# diplom.net
KiCad netlist of a schematic drawn in EAGLE
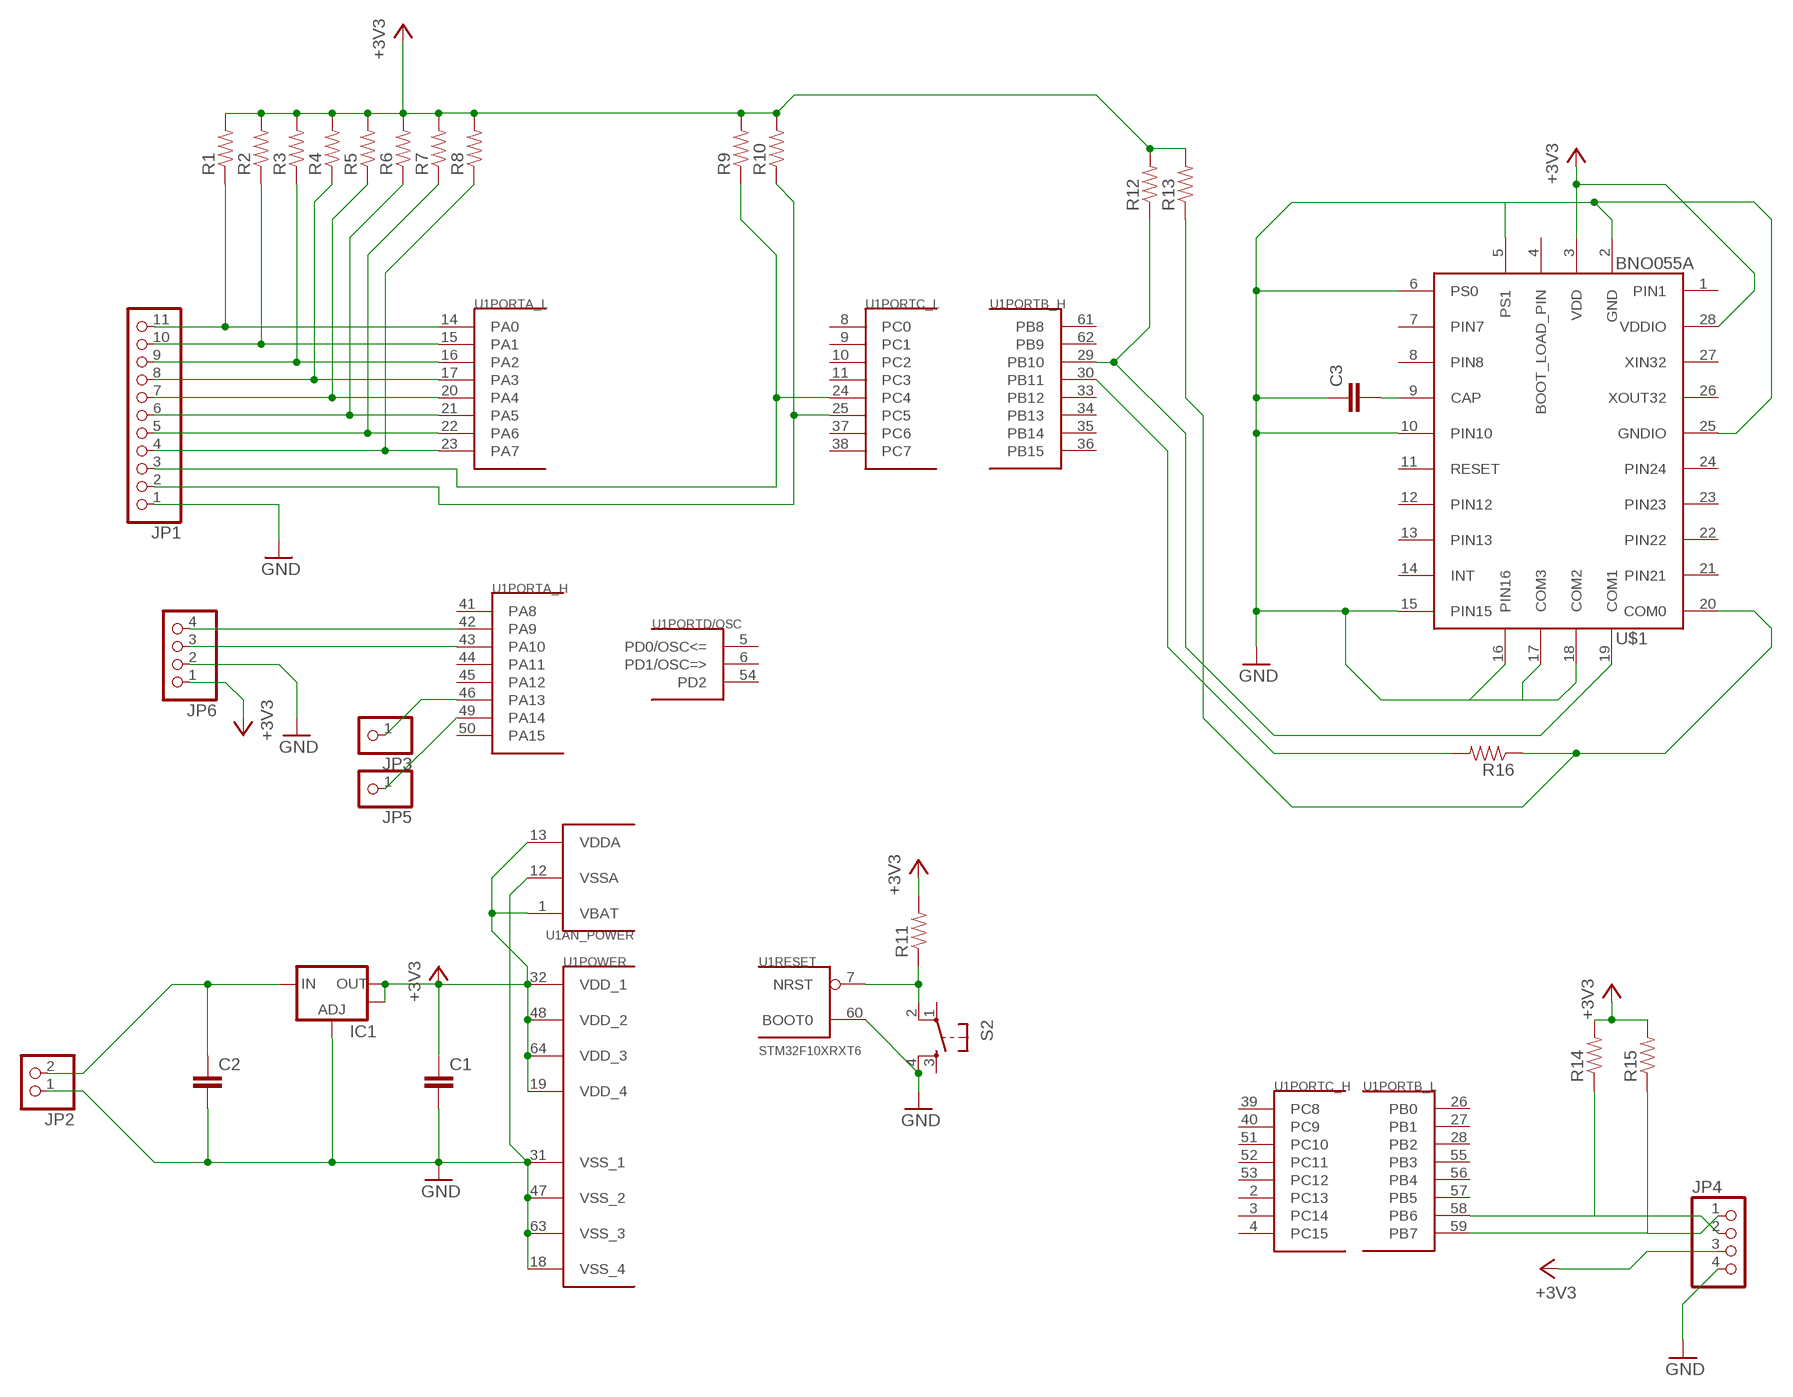
[diagram p0: schematic, sheet 1]

(export (version "E")
  (design (tool "Eeschema 10.0.6"))
  (components
    (comp (ref "C1")
      (value "CAP1206")
      (footprint "eagle-import:1206")
      (libsource (lib "eagle-import") (part "CAP1206"))
    )
    (comp (ref "C2")
      (value "CAP1206")
      (footprint "eagle-import:1206")
      (libsource (lib "eagle-import") (part "CAP1206"))
    )
    (comp (ref "C3")
      (value "CAP1206")
      (footprint "eagle-import:1206")
      (libsource (lib "eagle-import") (part "CAP1206"))
    )
    (comp (ref "IC1")
      (value "V_REG_LM1117SOT223")
      (footprint "eagle-import:SOT223")
      (libsource (lib "eagle-import") (part "V_REG_LM1117SOT223"))
    )
    (comp (ref "JP1")
      (value "PINHD-1X11_2.54")
      (footprint "eagle-import:1X11")
      (libsource (lib "eagle-import") (part "PINHD-1X11_2.54"))
    )
    (comp (ref "JP2")
      (value "PINHD-1X02_2.54")
      (footprint "eagle-import:1X02")
      (libsource (lib "eagle-import") (part "PINHD-1X02_2.54"))
    )
    (comp (ref "JP3")
      (value "PINHD-1X01_2.54")
      (footprint "eagle-import:1X01")
      (libsource (lib "eagle-import") (part "PINHD-1X01_2.54"))
    )
    (comp (ref "JP4")
      (value "PINHD-1X04_2.54")
      (footprint "eagle-import:1X04")
      (libsource (lib "eagle-import") (part "PINHD-1X04_2.54"))
    )
    (comp (ref "JP5")
      (value "PINHD-1X01_2.54")
      (footprint "eagle-import:1X01")
      (libsource (lib "eagle-import") (part "PINHD-1X01_2.54"))
    )
    (comp (ref "JP6")
      (value "PINHD-1X04_2.54")
      (footprint "eagle-import:1X04")
      (libsource (lib "eagle-import") (part "PINHD-1X04_2.54"))
    )
    (comp (ref "R1")
      (value "RESISTOR1206")
      (footprint "eagle-import:1206")
      (libsource (lib "eagle-import") (part "RESISTOR1206"))
    )
    (comp (ref "R2")
      (value "RESISTOR1206")
      (footprint "eagle-import:1206")
      (libsource (lib "eagle-import") (part "RESISTOR1206"))
    )
    (comp (ref "R3")
      (value "RESISTOR1206")
      (footprint "eagle-import:1206")
      (libsource (lib "eagle-import") (part "RESISTOR1206"))
    )
    (comp (ref "R4")
      (value "RESISTOR1206")
      (footprint "eagle-import:1206")
      (libsource (lib "eagle-import") (part "RESISTOR1206"))
    )
    (comp (ref "R5")
      (value "RESISTOR1206")
      (footprint "eagle-import:1206")
      (libsource (lib "eagle-import") (part "RESISTOR1206"))
    )
    (comp (ref "R6")
      (value "RESISTOR1206")
      (footprint "eagle-import:1206")
      (libsource (lib "eagle-import") (part "RESISTOR1206"))
    )
    (comp (ref "R7")
      (value "RESISTOR1206")
      (footprint "eagle-import:1206")
      (libsource (lib "eagle-import") (part "RESISTOR1206"))
    )
    (comp (ref "R8")
      (value "RESISTOR1206")
      (footprint "eagle-import:1206")
      (libsource (lib "eagle-import") (part "RESISTOR1206"))
    )
    (comp (ref "R9")
      (value "RESISTOR1206")
      (footprint "eagle-import:1206")
      (libsource (lib "eagle-import") (part "RESISTOR1206"))
    )
    (comp (ref "R10")
      (value "RESISTOR1206")
      (footprint "eagle-import:1206")
      (libsource (lib "eagle-import") (part "RESISTOR1206"))
    )
    (comp (ref "R11")
      (value "RESISTOR1206")
      (footprint "eagle-import:1206")
      (libsource (lib "eagle-import") (part "RESISTOR1206"))
    )
    (comp (ref "R12")
      (value "RESISTOR1206")
      (footprint "eagle-import:1206")
      (libsource (lib "eagle-import") (part "RESISTOR1206"))
    )
    (comp (ref "R13")
      (value "RESISTOR1206")
      (footprint "eagle-import:1206")
      (libsource (lib "eagle-import") (part "RESISTOR1206"))
    )
    (comp (ref "R14")
      (value "RESISTOR1206")
      (footprint "eagle-import:1206")
      (libsource (lib "eagle-import") (part "RESISTOR1206"))
    )
    (comp (ref "R15")
      (value "RESISTOR1206")
      (footprint "eagle-import:1206")
      (libsource (lib "eagle-import") (part "RESISTOR1206"))
    )
    (comp (ref "R16")
      (value "RESISTOR1206")
      (footprint "eagle-import:1206")
      (libsource (lib "eagle-import") (part "RESISTOR1206"))
    )
    (comp (ref "S2")
      (value "TAC_SWITCHPTH")
      (footprint "eagle-import:TACTILE-PTH")
      (libsource (lib "eagle-import") (part "TAC_SWITCHPTH"))
    )
    (comp (ref "U$1")
      (value "BNO055A")
      (footprint "eagle-import:BNO055")
      (libsource (lib "eagle-import") (part "BNO055A"))
    )
    (comp (ref "U1")
      (value "STM32F10XRXT6")
      (footprint "eagle-import:TQFP64")
      (libsource (lib "eagle-import") (part "STM32F10XRXT6"))
    )
  )
  (nets
    (net (code "1") (name "+3V3") (class "Default")
      (node (ref "C1") (pin "1") (pinfunction "1_1") (pintype "passive"))
      (node (ref "IC1") (pin "2") (pinfunction "OUT_2") (pintype "output"))
      (node (ref "IC1") (pin "4") (pinfunction "OUT_4") (pintype "output"))
      (node (ref "JP4") (pin "3") (pinfunction "3_3") (pintype "passive"))
      (node (ref "JP6") (pin "1") (pinfunction "1_1") (pintype "passive"))
      (node (ref "R1") (pin "2") (pinfunction "2_2") (pintype "passive"))
      (node (ref "R10") (pin "2") (pinfunction "2_2") (pintype "passive"))
      (node (ref "R11") (pin "2") (pinfunction "2_2") (pintype "passive"))
      (node (ref "R12") (pin "2") (pinfunction "2_2") (pintype "passive"))
      (node (ref "R13") (pin "2") (pinfunction "2_2") (pintype "passive"))
      (node (ref "R14") (pin "2") (pinfunction "2_2") (pintype "passive"))
      (node (ref "R15") (pin "2") (pinfunction "2_2") (pintype "passive"))
      (node (ref "R2") (pin "2") (pinfunction "2_2") (pintype "passive"))
      (node (ref "R3") (pin "2") (pinfunction "2_2") (pintype "passive"))
      (node (ref "R4") (pin "2") (pinfunction "2_2") (pintype "passive"))
      (node (ref "R5") (pin "2") (pinfunction "2_2") (pintype "passive"))
      (node (ref "R6") (pin "2") (pinfunction "2_2") (pintype "passive"))
      (node (ref "R7") (pin "2") (pinfunction "2_2") (pintype "passive"))
      (node (ref "R8") (pin "2") (pinfunction "2_2") (pintype "passive"))
      (node (ref "R9") (pin "2") (pinfunction "2_2") (pintype "passive"))
      (node (ref "U$1") (pin "28") (pinfunction "VDDIO_28") (pintype "bidirectional"))
      (node (ref "U$1") (pin "3") (pinfunction "VDD_3") (pintype "bidirectional"))
      (node (ref "U1") (pin "1") (pinfunction "VBAT_1") (pintype "power_in"))
      (node (ref "U1") (pin "13") (pinfunction "VDDA_13") (pintype "power_in"))
      (node (ref "U1") (pin "19") (pinfunction "VDD_4_19") (pintype "power_in"))
      (node (ref "U1") (pin "32") (pinfunction "VDD_1_32") (pintype "power_in"))
      (node (ref "U1") (pin "48") (pinfunction "VDD_2_48") (pintype "power_in"))
      (node (ref "U1") (pin "64") (pinfunction "VDD_3_64") (pintype "power_in"))
    )
    (net (code "2") (name "GND") (class "Default")
      (node (ref "C1") (pin "2") (pinfunction "2_2") (pintype "passive"))
      (node (ref "C2") (pin "2") (pinfunction "2_2") (pintype "passive"))
      (node (ref "C3") (pin "1") (pinfunction "1_1") (pintype "passive"))
      (node (ref "IC1") (pin "1") (pinfunction "ADJ_1") (pintype "input"))
      (node (ref "JP1") (pin "1") (pinfunction "1_1") (pintype "passive"))
      (node (ref "JP2") (pin "1") (pinfunction "1_1") (pintype "passive"))
      (node (ref "JP4") (pin "4") (pinfunction "4_4") (pintype "passive"))
      (node (ref "JP6") (pin "2") (pinfunction "2_2") (pintype "passive"))
      (node (ref "S2") (pin "4") (pinfunction "4_4") (pintype "passive"))
      (node (ref "U$1") (pin "10") (pinfunction "PIN10_10") (pintype "bidirectional"))
      (node (ref "U$1") (pin "15") (pinfunction "PIN15_15") (pintype "bidirectional"))
      (node (ref "U$1") (pin "16") (pinfunction "PIN16_16") (pintype "bidirectional"))
      (node (ref "U$1") (pin "17") (pinfunction "COM3_17") (pintype "bidirectional"))
      (node (ref "U$1") (pin "18") (pinfunction "COM2_18") (pintype "bidirectional"))
      (node (ref "U$1") (pin "2") (pinfunction "GND_2") (pintype "bidirectional"))
      (node (ref "U$1") (pin "25") (pinfunction "GNDIO_25") (pintype "bidirectional"))
      (node (ref "U$1") (pin "5") (pinfunction "PS1_5") (pintype "bidirectional"))
      (node (ref "U$1") (pin "6") (pinfunction "PS0_6") (pintype "bidirectional"))
      (node (ref "U1") (pin "12") (pinfunction "VSSA_12") (pintype "power_in"))
      (node (ref "U1") (pin "18") (pinfunction "VSS_4_18") (pintype "power_in"))
      (node (ref "U1") (pin "31") (pinfunction "VSS_1_31") (pintype "power_in"))
      (node (ref "U1") (pin "47") (pinfunction "VSS_2_47") (pintype "power_in"))
      (node (ref "U1") (pin "60") (pinfunction "BOOT0_60") (pintype "input"))
      (node (ref "U1") (pin "63") (pinfunction "VSS_3_63") (pintype "power_in"))
    )
    (net (code "3") (name "Net-(IC1-IN)") (class "Default")
      (node (ref "C2") (pin "1") (pinfunction "1_1") (pintype "passive"))
      (node (ref "IC1") (pin "3") (pinfunction "IN_3") (pintype "input"))
      (node (ref "JP2") (pin "2") (pinfunction "2_2") (pintype "passive"))
    )
    (net (code "4") (name "Net-(U$1-CAP)") (class "Default")
      (node (ref "C3") (pin "2") (pinfunction "2_2") (pintype "passive"))
      (node (ref "U$1") (pin "9") (pinfunction "CAP_9") (pintype "bidirectional"))
    )
    (net (code "5") (name "Net-(U$1-COM0)") (class "Default")
      (node (ref "R13") (pin "1") (pinfunction "1_1") (pintype "passive"))
      (node (ref "R16") (pin "1") (pinfunction "1_1") (pintype "passive"))
      (node (ref "U$1") (pin "20") (pinfunction "COM0_20") (pintype "bidirectional"))
    )
    (net (code "6") (name "Net-(U$1-COM1)") (class "Default")
      (node (ref "R12") (pin "1") (pinfunction "1_1") (pintype "passive"))
      (node (ref "U$1") (pin "19") (pinfunction "COM1_19") (pintype "bidirectional"))
      (node (ref "U1") (pin "29") (pinfunction "PB10_29") (pintype "bidirectional"))
    )
    (net (code "7") (name "Net-(U1B-PA9)") (class "Default")
      (node (ref "JP6") (pin "4") (pinfunction "4_4") (pintype "passive"))
      (node (ref "U1") (pin "42") (pinfunction "PA9_42") (pintype "bidirectional"))
    )
    (net (code "8") (name "Net-(U1B-PA10)") (class "Default")
      (node (ref "JP6") (pin "3") (pinfunction "3_3") (pintype "passive"))
      (node (ref "U1") (pin "43") (pinfunction "PA10_43") (pintype "bidirectional"))
    )
    (net (code "9") (name "Net-(U1B-PA13)") (class "Default")
      (node (ref "JP3") (pin "1") (pinfunction "1_1") (pintype "passive"))
      (node (ref "U1") (pin "46") (pinfunction "PA13_46") (pintype "bidirectional"))
    )
    (net (code "10") (name "Net-(U1B-PA14)") (class "Default")
      (node (ref "JP5") (pin "1") (pinfunction "1_1") (pintype "passive"))
      (node (ref "U1") (pin "49") (pinfunction "PA14_49") (pintype "bidirectional"))
    )
    (net (code "11") (name "Net-(U1C-PA0)") (class "Default")
      (node (ref "JP1") (pin "11") (pinfunction "11_11") (pintype "passive"))
      (node (ref "R1") (pin "1") (pinfunction "1_1") (pintype "passive"))
      (node (ref "U1") (pin "14") (pinfunction "PA0_14") (pintype "bidirectional"))
    )
    (net (code "12") (name "Net-(U1C-PA1)") (class "Default")
      (node (ref "JP1") (pin "10") (pinfunction "10_10") (pintype "passive"))
      (node (ref "R2") (pin "1") (pinfunction "1_1") (pintype "passive"))
      (node (ref "U1") (pin "15") (pinfunction "PA1_15") (pintype "bidirectional"))
    )
    (net (code "13") (name "Net-(U1C-PA2)") (class "Default")
      (node (ref "JP1") (pin "9") (pinfunction "9_9") (pintype "passive"))
      (node (ref "R3") (pin "1") (pinfunction "1_1") (pintype "passive"))
      (node (ref "U1") (pin "16") (pinfunction "PA2_16") (pintype "bidirectional"))
    )
    (net (code "14") (name "Net-(U1C-PA3)") (class "Default")
      (node (ref "JP1") (pin "8") (pinfunction "8_8") (pintype "passive"))
      (node (ref "R4") (pin "1") (pinfunction "1_1") (pintype "passive"))
      (node (ref "U1") (pin "17") (pinfunction "PA3_17") (pintype "bidirectional"))
    )
    (net (code "15") (name "Net-(U1C-PA4)") (class "Default")
      (node (ref "JP1") (pin "7") (pinfunction "7_7") (pintype "passive"))
      (node (ref "R5") (pin "1") (pinfunction "1_1") (pintype "passive"))
      (node (ref "U1") (pin "20") (pinfunction "PA4_20") (pintype "bidirectional"))
    )
    (net (code "16") (name "Net-(U1C-PA5)") (class "Default")
      (node (ref "JP1") (pin "6") (pinfunction "6_6") (pintype "passive"))
      (node (ref "R6") (pin "1") (pinfunction "1_1") (pintype "passive"))
      (node (ref "U1") (pin "21") (pinfunction "PA5_21") (pintype "bidirectional"))
    )
    (net (code "17") (name "Net-(U1C-PA6)") (class "Default")
      (node (ref "JP1") (pin "5") (pinfunction "5_5") (pintype "passive"))
      (node (ref "R7") (pin "1") (pinfunction "1_1") (pintype "passive"))
      (node (ref "U1") (pin "22") (pinfunction "PA6_22") (pintype "bidirectional"))
    )
    (net (code "18") (name "Net-(U1C-PA7)") (class "Default")
      (node (ref "JP1") (pin "4") (pinfunction "4_4") (pintype "passive"))
      (node (ref "R8") (pin "1") (pinfunction "1_1") (pintype "passive"))
      (node (ref "U1") (pin "23") (pinfunction "PA7_23") (pintype "bidirectional"))
    )
    (net (code "19") (name "Net-(U1D-PB11)") (class "Default")
      (node (ref "R16") (pin "2") (pinfunction "2_2") (pintype "passive"))
      (node (ref "U1") (pin "30") (pinfunction "PB11_30") (pintype "bidirectional"))
    )
    (net (code "20") (name "Net-(U1E-PB6)") (class "Default")
      (node (ref "JP4") (pin "2") (pinfunction "2_2") (pintype "passive"))
      (node (ref "R14") (pin "1") (pinfunction "1_1") (pintype "passive"))
      (node (ref "U1") (pin "58") (pinfunction "PB6_58") (pintype "bidirectional"))
    )
    (net (code "21") (name "Net-(U1E-PB7)") (class "Default")
      (node (ref "JP4") (pin "1") (pinfunction "1_1") (pintype "passive"))
      (node (ref "R15") (pin "1") (pinfunction "1_1") (pintype "passive"))
      (node (ref "U1") (pin "59") (pinfunction "PB7_59") (pintype "bidirectional"))
    )
    (net (code "22") (name "Net-(U1G-PC4)") (class "Default")
      (node (ref "JP1") (pin "3") (pinfunction "3_3") (pintype "passive"))
      (node (ref "R9") (pin "1") (pinfunction "1_1") (pintype "passive"))
      (node (ref "U1") (pin "24") (pinfunction "PC4_24") (pintype "bidirectional"))
    )
    (net (code "23") (name "Net-(U1G-PC5)") (class "Default")
      (node (ref "JP1") (pin "2") (pinfunction "2_2") (pintype "passive"))
      (node (ref "R10") (pin "1") (pinfunction "1_1") (pintype "passive"))
      (node (ref "U1") (pin "25") (pinfunction "PC5_25") (pintype "bidirectional"))
    )
    (net (code "24") (name "Net-(U1J-NRST)") (class "Default")
      (node (ref "R11") (pin "1") (pinfunction "1_1") (pintype "passive"))
      (node (ref "S2") (pin "2") (pinfunction "2_2") (pintype "passive"))
      (node (ref "U1") (pin "7") (pinfunction "NRST_7") (pintype "input"))
    )
    (net (code "25") (name "unconnected-(S2-Pad1)") (class "Default")
      (node (ref "S2") (pin "1") (pinfunction "1_1") (pintype "passive"))
    )
    (net (code "26") (name "unconnected-(S2-Pad3)") (class "Default")
      (node (ref "S2") (pin "3") (pinfunction "3_3") (pintype "passive"))
    )
    (net (code "27") (name "unconnected-(U$1-BOOT_LOAD_PIN-Pad4)") (class "Default")
      (node (ref "U$1") (pin "4") (pinfunction "BOOT_LOAD_PIN_4") (pintype "bidirectional"))
    )
    (net (code "28") (name "unconnected-(U$1-INT-Pad14)") (class "Default")
      (node (ref "U$1") (pin "14") (pinfunction "INT_14") (pintype "bidirectional"))
    )
    (net (code "29") (name "unconnected-(U$1-PIN1-Pad1)") (class "Default")
      (node (ref "U$1") (pin "1") (pinfunction "PIN1_1") (pintype "bidirectional"))
    )
    (net (code "30") (name "unconnected-(U$1-PIN7-Pad7)") (class "Default")
      (node (ref "U$1") (pin "7") (pinfunction "PIN7_7") (pintype "bidirectional"))
    )
    (net (code "31") (name "unconnected-(U$1-PIN8-Pad8)") (class "Default")
      (node (ref "U$1") (pin "8") (pinfunction "PIN8_8") (pintype "bidirectional"))
    )
    (net (code "32") (name "unconnected-(U$1-PIN12-Pad12)") (class "Default")
      (node (ref "U$1") (pin "12") (pinfunction "PIN12_12") (pintype "bidirectional"))
    )
    (net (code "33") (name "unconnected-(U$1-PIN13-Pad13)") (class "Default")
      (node (ref "U$1") (pin "13") (pinfunction "PIN13_13") (pintype "bidirectional"))
    )
    (net (code "34") (name "unconnected-(U$1-PIN21-Pad21)") (class "Default")
      (node (ref "U$1") (pin "21") (pinfunction "PIN21_21") (pintype "bidirectional"))
    )
    (net (code "35") (name "unconnected-(U$1-PIN22-Pad22)") (class "Default")
      (node (ref "U$1") (pin "22") (pinfunction "PIN22_22") (pintype "bidirectional"))
    )
    (net (code "36") (name "unconnected-(U$1-PIN23-Pad23)") (class "Default")
      (node (ref "U$1") (pin "23") (pinfunction "PIN23_23") (pintype "bidirectional"))
    )
    (net (code "37") (name "unconnected-(U$1-PIN24-Pad24)") (class "Default")
      (node (ref "U$1") (pin "24") (pinfunction "PIN24_24") (pintype "bidirectional"))
    )
    (net (code "38") (name "unconnected-(U$1-RESET-Pad11)") (class "Default")
      (node (ref "U$1") (pin "11") (pinfunction "RESET_11") (pintype "bidirectional"))
    )
    (net (code "39") (name "unconnected-(U$1-XIN32-Pad27)") (class "Default")
      (node (ref "U$1") (pin "27") (pinfunction "XIN32_27") (pintype "bidirectional"))
    )
    (net (code "40") (name "unconnected-(U$1-XOUT32-Pad26)") (class "Default")
      (node (ref "U$1") (pin "26") (pinfunction "XOUT32_26") (pintype "bidirectional"))
    )
    (net (code "41") (name "unconnected-(U1B-PA8-Pad41)") (class "Default")
      (node (ref "U1") (pin "41") (pinfunction "PA8_41") (pintype "bidirectional"))
    )
    (net (code "42") (name "unconnected-(U1B-PA11-Pad44)") (class "Default")
      (node (ref "U1") (pin "44") (pinfunction "PA11_44") (pintype "bidirectional"))
    )
    (net (code "43") (name "unconnected-(U1B-PA12-Pad45)") (class "Default")
      (node (ref "U1") (pin "45") (pinfunction "PA12_45") (pintype "bidirectional"))
    )
    (net (code "44") (name "unconnected-(U1B-PA15-Pad50)") (class "Default")
      (node (ref "U1") (pin "50") (pinfunction "PA15_50") (pintype "bidirectional"))
    )
    (net (code "45") (name "unconnected-(U1D-PB8-Pad61)") (class "Default")
      (node (ref "U1") (pin "61") (pinfunction "PB8_61") (pintype "bidirectional"))
    )
    (net (code "46") (name "unconnected-(U1D-PB9-Pad62)") (class "Default")
      (node (ref "U1") (pin "62") (pinfunction "PB9_62") (pintype "bidirectional"))
    )
    (net (code "47") (name "unconnected-(U1D-PB12-Pad33)") (class "Default")
      (node (ref "U1") (pin "33") (pinfunction "PB12_33") (pintype "bidirectional"))
    )
    (net (code "48") (name "unconnected-(U1D-PB13-Pad34)") (class "Default")
      (node (ref "U1") (pin "34") (pinfunction "PB13_34") (pintype "bidirectional"))
    )
    (net (code "49") (name "unconnected-(U1D-PB14-Pad35)") (class "Default")
      (node (ref "U1") (pin "35") (pinfunction "PB14_35") (pintype "bidirectional"))
    )
    (net (code "50") (name "unconnected-(U1D-PB15-Pad36)") (class "Default")
      (node (ref "U1") (pin "36") (pinfunction "PB15_36") (pintype "bidirectional"))
    )
    (net (code "51") (name "unconnected-(U1E-PB0-Pad26)") (class "Default")
      (node (ref "U1") (pin "26") (pinfunction "PB0_26") (pintype "bidirectional"))
    )
    (net (code "52") (name "unconnected-(U1E-PB1-Pad27)") (class "Default")
      (node (ref "U1") (pin "27") (pinfunction "PB1_27") (pintype "bidirectional"))
    )
    (net (code "53") (name "unconnected-(U1E-PB2-Pad28)") (class "Default")
      (node (ref "U1") (pin "28") (pinfunction "PB2_28") (pintype "bidirectional"))
    )
    (net (code "54") (name "unconnected-(U1E-PB3-Pad55)") (class "Default")
      (node (ref "U1") (pin "55") (pinfunction "PB3_55") (pintype "bidirectional"))
    )
    (net (code "55") (name "unconnected-(U1E-PB4-Pad56)") (class "Default")
      (node (ref "U1") (pin "56") (pinfunction "PB4_56") (pintype "bidirectional"))
    )
    (net (code "56") (name "unconnected-(U1E-PB5-Pad57)") (class "Default")
      (node (ref "U1") (pin "57") (pinfunction "PB5_57") (pintype "bidirectional"))
    )
    (net (code "57") (name "unconnected-(U1F-PC8-Pad39)") (class "Default")
      (node (ref "U1") (pin "39") (pinfunction "PC8_39") (pintype "bidirectional"))
    )
    (net (code "58") (name "unconnected-(U1F-PC9-Pad40)") (class "Default")
      (node (ref "U1") (pin "40") (pinfunction "PC9_40") (pintype "bidirectional"))
    )
    (net (code "59") (name "unconnected-(U1F-PC10-Pad51)") (class "Default")
      (node (ref "U1") (pin "51") (pinfunction "PC10_51") (pintype "bidirectional"))
    )
    (net (code "60") (name "unconnected-(U1F-PC11-Pad52)") (class "Default")
      (node (ref "U1") (pin "52") (pinfunction "PC11_52") (pintype "bidirectional"))
    )
    (net (code "61") (name "unconnected-(U1F-PC12-Pad53)") (class "Default")
      (node (ref "U1") (pin "53") (pinfunction "PC12_53") (pintype "bidirectional"))
    )
    (net (code "62") (name "unconnected-(U1F-PC13-Pad2)") (class "Default")
      (node (ref "U1") (pin "2") (pinfunction "PC13_2") (pintype "bidirectional"))
    )
    (net (code "63") (name "unconnected-(U1F-PC14-Pad3)") (class "Default")
      (node (ref "U1") (pin "3") (pinfunction "PC14_3") (pintype "bidirectional"))
    )
    (net (code "64") (name "unconnected-(U1F-PC15-Pad4)") (class "Default")
      (node (ref "U1") (pin "4") (pinfunction "PC15_4") (pintype "bidirectional"))
    )
    (net (code "65") (name "unconnected-(U1G-PC0-Pad8)") (class "Default")
      (node (ref "U1") (pin "8") (pinfunction "PC0_8") (pintype "bidirectional"))
    )
    (net (code "66") (name "unconnected-(U1G-PC1-Pad9)") (class "Default")
      (node (ref "U1") (pin "9") (pinfunction "PC1_9") (pintype "bidirectional"))
    )
    (net (code "67") (name "unconnected-(U1G-PC2-Pad10)") (class "Default")
      (node (ref "U1") (pin "10") (pinfunction "PC2_10") (pintype "bidirectional"))
    )
    (net (code "68") (name "unconnected-(U1G-PC3-Pad11)") (class "Default")
      (node (ref "U1") (pin "11") (pinfunction "PC3_11") (pintype "bidirectional"))
    )
    (net (code "69") (name "unconnected-(U1G-PC6-Pad37)") (class "Default")
      (node (ref "U1") (pin "37") (pinfunction "PC6_37") (pintype "bidirectional"))
    )
    (net (code "70") (name "unconnected-(U1G-PC7-Pad38)") (class "Default")
      (node (ref "U1") (pin "38") (pinfunction "PC7_38") (pintype "bidirectional"))
    )
    (net (code "71") (name "unconnected-(U1H-PD0{slash}OSC<=-Pad5)") (class "Default")
      (node (ref "U1") (pin "5") (pinfunction "PD0/OSC<=_5") (pintype "bidirectional"))
    )
    (net (code "72") (name "unconnected-(U1H-PD1{slash}OSC=>-Pad6)") (class "Default")
      (node (ref "U1") (pin "6") (pinfunction "PD1/OSC=>_6") (pintype "bidirectional"))
    )
    (net (code "73") (name "unconnected-(U1H-PD2-Pad54)") (class "Default")
      (node (ref "U1") (pin "54") (pinfunction "PD2_54") (pintype "bidirectional"))
    )
  )
)
